# PSU.net
KiCad netlist of a schematic drawn in EAGLE
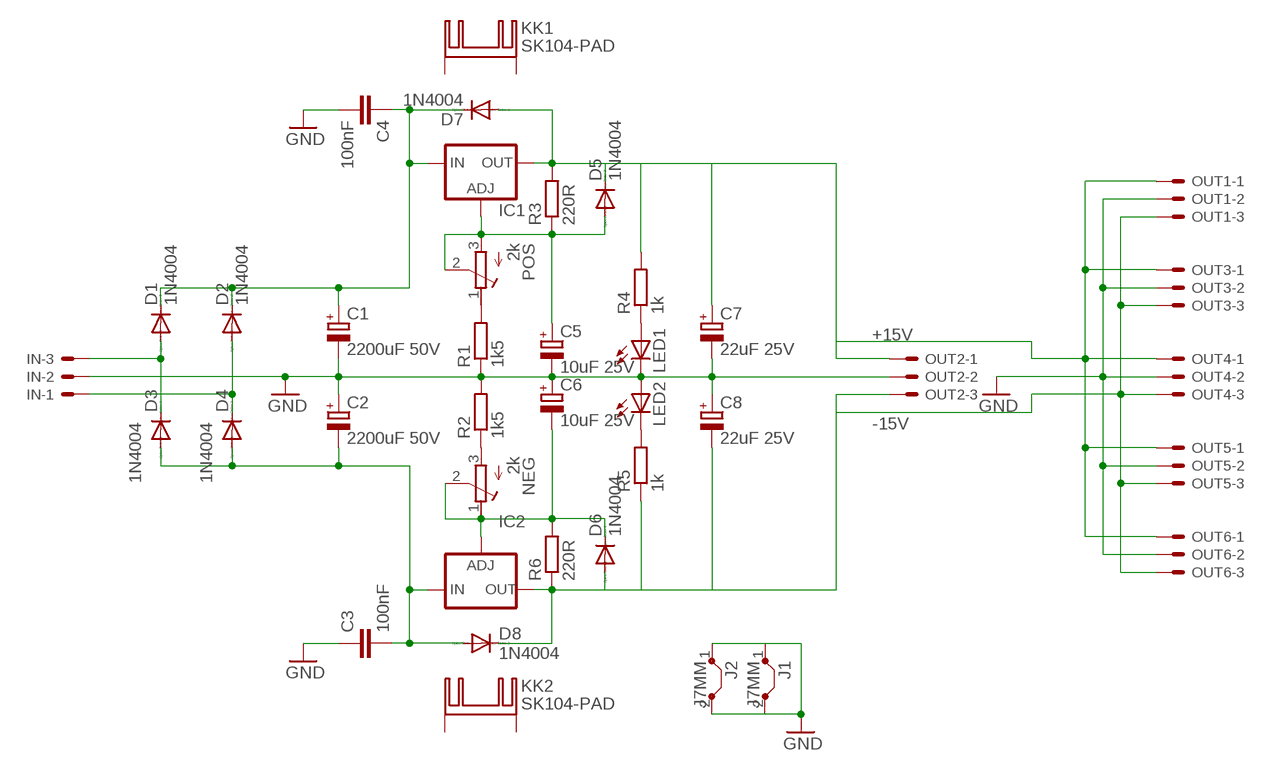
[diagram p0: schematic, sheet 1]

(export (version "E")
  (design (tool "Eeschema 10.0.6"))
  (components
    (comp (ref "C1")
      (value "2200uF 50V")
      (footprint "eagle-import:E7,5-16")
      (libsource (lib "eagle-import") (part "CPOL-EUE7.5-16"))
    )
    (comp (ref "C2")
      (value "2200uF 50V")
      (footprint "eagle-import:E7,5-16")
      (libsource (lib "eagle-import") (part "CPOL-EUE7.5-16"))
    )
    (comp (ref "C3")
      (value "100nF")
      (footprint "eagle-import:C050-025X075")
      (libsource (lib "eagle-import") (part "C-EU050-025X075"))
    )
    (comp (ref "C4")
      (value "100nF")
      (footprint "eagle-import:C050-025X075")
      (libsource (lib "eagle-import") (part "C-EU050-025X075"))
    )
    (comp (ref "C5")
      (value "10uF 25V")
      (footprint "eagle-import:E2,5-5")
      (libsource (lib "eagle-import") (part "CPOL-EUE2.5-5"))
    )
    (comp (ref "C6")
      (value "10uF 25V")
      (footprint "eagle-import:E2,5-5")
      (libsource (lib "eagle-import") (part "CPOL-EUE2.5-5"))
    )
    (comp (ref "C7")
      (value "22uF 25V")
      (footprint "eagle-import:E2,5-5")
      (libsource (lib "eagle-import") (part "CPOL-EUE2.5-5"))
    )
    (comp (ref "C8")
      (value "22uF 25V")
      (footprint "eagle-import:E2,5-5")
      (libsource (lib "eagle-import") (part "CPOL-EUE2.5-5"))
    )
    (comp (ref "D1")
      (value "1N4004")
      (footprint "eagle-import:DO41-10")
      (libsource (lib "eagle-import") (part "1N4004"))
    )
    (comp (ref "D2")
      (value "1N4004")
      (footprint "eagle-import:DO41-10")
      (libsource (lib "eagle-import") (part "1N4004"))
    )
    (comp (ref "D3")
      (value "1N4004")
      (footprint "eagle-import:DO41-10")
      (libsource (lib "eagle-import") (part "1N4004"))
    )
    (comp (ref "D4")
      (value "1N4004")
      (footprint "eagle-import:DO41-10")
      (libsource (lib "eagle-import") (part "1N4004"))
    )
    (comp (ref "D5")
      (value "1N4004")
      (footprint "eagle-import:DO41-10")
      (libsource (lib "eagle-import") (part "1N4004"))
    )
    (comp (ref "D6")
      (value "1N4004")
      (footprint "eagle-import:DO41-10")
      (libsource (lib "eagle-import") (part "1N4004"))
    )
    (comp (ref "D7")
      (value "1N4004")
      (footprint "eagle-import:DO41-10")
      (libsource (lib "eagle-import") (part "1N4004"))
    )
    (comp (ref "D8")
      (value "1N4004")
      (footprint "eagle-import:DO41-10")
      (libsource (lib "eagle-import") (part "1N4004"))
    )
    (comp (ref "IC1")
      (value "LM317TS")
      (footprint "eagle-import:317TS")
      (libsource (lib "eagle-import") (part "LM317TS"))
    )
    (comp (ref "IC2")
      (value "LM337TS")
      (footprint "eagle-import:337TS")
      (libsource (lib "eagle-import") (part "LM337TS"))
    )
    (comp (ref "IN")
      (value "KK-156-3")
      (footprint "eagle-import:KK-156-3")
      (libsource (lib "eagle-import") (part "KK-156-3"))
    )
    (comp (ref "J1")
      (value "J7MM")
      (footprint "eagle-import:07")
      (libsource (lib "eagle-import") (part "J7MM"))
    )
    (comp (ref "J2")
      (value "J7MM")
      (footprint "eagle-import:07")
      (libsource (lib "eagle-import") (part "J7MM"))
    )
    (comp (ref "KK1")
      (value "SK104-PAD")
      (footprint "eagle-import:SK104-PAD")
      (libsource (lib "eagle-import") (part "SK104-PAD"))
    )
    (comp (ref "KK2")
      (value "SK104-PAD")
      (footprint "eagle-import:SK104-PAD")
      (libsource (lib "eagle-import") (part "SK104-PAD"))
    )
    (comp (ref "LED1")
      (value "LED3MM")
      (footprint "eagle-import:LED3MM")
      (libsource (lib "eagle-import") (part "LED3MM"))
    )
    (comp (ref "LED2")
      (value "LED3MM")
      (footprint "eagle-import:LED3MM")
      (libsource (lib "eagle-import") (part "LED3MM"))
    )
    (comp (ref "NEG")
      (value "2k")
      (footprint "eagle-import:RTRIMT93YA")
      (libsource (lib "eagle-import") (part "R-TRIMMT93YA"))
    )
    (comp (ref "OUT1")
      (value "KK-156-3")
      (footprint "eagle-import:KK-156-3")
      (libsource (lib "eagle-import") (part "KK-156-3"))
    )
    (comp (ref "OUT2")
      (value "KK-156-3")
      (footprint "eagle-import:KK-156-3")
      (libsource (lib "eagle-import") (part "KK-156-3"))
    )
    (comp (ref "OUT3")
      (value "KK-156-3")
      (footprint "eagle-import:KK-156-3")
      (libsource (lib "eagle-import") (part "KK-156-3"))
    )
    (comp (ref "OUT4")
      (value "KK-156-3")
      (footprint "eagle-import:KK-156-3")
      (libsource (lib "eagle-import") (part "KK-156-3"))
    )
    (comp (ref "OUT5")
      (value "KK-156-3")
      (footprint "eagle-import:KK-156-3")
      (libsource (lib "eagle-import") (part "KK-156-3"))
    )
    (comp (ref "OUT6")
      (value "KK-156-3")
      (footprint "eagle-import:KK-156-3")
      (libsource (lib "eagle-import") (part "KK-156-3"))
    )
    (comp (ref "POS")
      (value "2k")
      (footprint "eagle-import:RTRIMT93YA")
      (libsource (lib "eagle-import") (part "R-TRIMMT93YA"))
    )
    (comp (ref "R1")
      (value "1k5")
      (footprint "eagle-import:0207_7")
      (libsource (lib "eagle-import") (part "R-EU_0207/7"))
    )
    (comp (ref "R2")
      (value "1k5")
      (footprint "eagle-import:0207_7")
      (libsource (lib "eagle-import") (part "R-EU_0207/7"))
    )
    (comp (ref "R3")
      (value "220R")
      (footprint "eagle-import:0207_7")
      (libsource (lib "eagle-import") (part "R-EU_0207/7"))
    )
    (comp (ref "R4")
      (value "1k")
      (footprint "eagle-import:0207_7")
      (libsource (lib "eagle-import") (part "R-EU_0207/7"))
    )
    (comp (ref "R5")
      (value "1k")
      (footprint "eagle-import:0207_7")
      (libsource (lib "eagle-import") (part "R-EU_0207/7"))
    )
    (comp (ref "R6")
      (value "220R")
      (footprint "eagle-import:0207_7")
      (libsource (lib "eagle-import") (part "R-EU_0207/7"))
    )
  )
  (nets
    (net (code "1") (name "/+15V") (class "Default")
      (node (ref "C7") (pin "+") (pinfunction "+_+") (pintype "passive"))
      (node (ref "D5") (pin "C") (pinfunction "C_C") (pintype "passive"))
      (node (ref "D7") (pin "A") (pinfunction "A_A") (pintype "passive"))
      (node (ref "IC1") (pin "2") (pinfunction "OUT_2") (pintype "passive"))
      (node (ref "OUT1") (pin "1") (pinfunction "S_1") (pintype "passive"))
      (node (ref "OUT2") (pin "1") (pinfunction "S_1") (pintype "passive"))
      (node (ref "OUT3") (pin "1") (pinfunction "S_1") (pintype "passive"))
      (node (ref "OUT4") (pin "1") (pinfunction "S_1") (pintype "passive"))
      (node (ref "OUT5") (pin "1") (pinfunction "S_1") (pintype "passive"))
      (node (ref "OUT6") (pin "1") (pinfunction "S_1") (pintype "passive"))
      (node (ref "R3") (pin "2") (pinfunction "2_2") (pintype "passive"))
      (node (ref "R4") (pin "2") (pinfunction "2_2") (pintype "passive"))
    )
    (net (code "2") (name "/-15V") (class "Default")
      (node (ref "C8") (pin "-") (pinfunction "-_-") (pintype "passive"))
      (node (ref "D6") (pin "A") (pinfunction "A_A") (pintype "passive"))
      (node (ref "D8") (pin "C") (pinfunction "C_C") (pintype "passive"))
      (node (ref "IC2") (pin "3") (pinfunction "OUT_3") (pintype "passive"))
      (node (ref "OUT1") (pin "3") (pinfunction "S_3") (pintype "passive"))
      (node (ref "OUT2") (pin "3") (pinfunction "S_3") (pintype "passive"))
      (node (ref "OUT3") (pin "3") (pinfunction "S_3") (pintype "passive"))
      (node (ref "OUT4") (pin "3") (pinfunction "S_3") (pintype "passive"))
      (node (ref "OUT5") (pin "3") (pinfunction "S_3") (pintype "passive"))
      (node (ref "OUT6") (pin "3") (pinfunction "S_3") (pintype "passive"))
      (node (ref "R5") (pin "1") (pinfunction "1_1") (pintype "passive"))
      (node (ref "R6") (pin "1") (pinfunction "1_1") (pintype "passive"))
    )
    (net (code "3") (name "GND") (class "Default")
      (node (ref "C1") (pin "-") (pinfunction "-_-") (pintype "passive"))
      (node (ref "C2") (pin "+") (pinfunction "+_+") (pintype "passive"))
      (node (ref "C3") (pin "1") (pinfunction "1_1") (pintype "passive"))
      (node (ref "C4") (pin "2") (pinfunction "2_2") (pintype "passive"))
      (node (ref "C5") (pin "-") (pinfunction "-_-") (pintype "passive"))
      (node (ref "C6") (pin "+") (pinfunction "+_+") (pintype "passive"))
      (node (ref "C7") (pin "-") (pinfunction "-_-") (pintype "passive"))
      (node (ref "C8") (pin "+") (pinfunction "+_+") (pintype "passive"))
      (node (ref "IN") (pin "2") (pinfunction "S_2") (pintype "passive"))
      (node (ref "J1") (pin "1") (pinfunction "1_1") (pintype "passive"))
      (node (ref "J1") (pin "2") (pinfunction "2_2") (pintype "passive"))
      (node (ref "J2") (pin "1") (pinfunction "1_1") (pintype "passive"))
      (node (ref "J2") (pin "2") (pinfunction "2_2") (pintype "passive"))
      (node (ref "LED1") (pin "K") (pinfunction "C_K") (pintype "passive"))
      (node (ref "LED2") (pin "A") (pinfunction "A_A") (pintype "passive"))
      (node (ref "OUT1") (pin "2") (pinfunction "S_2") (pintype "passive"))
      (node (ref "OUT2") (pin "2") (pinfunction "S_2") (pintype "passive"))
      (node (ref "OUT3") (pin "2") (pinfunction "S_2") (pintype "passive"))
      (node (ref "OUT4") (pin "2") (pinfunction "S_2") (pintype "passive"))
      (node (ref "OUT5") (pin "2") (pinfunction "S_2") (pintype "passive"))
      (node (ref "OUT6") (pin "2") (pinfunction "S_2") (pintype "passive"))
      (node (ref "R1") (pin "1") (pinfunction "1_1") (pintype "passive"))
      (node (ref "R2") (pin "2") (pinfunction "2_2") (pintype "passive"))
    )
    (net (code "4") (name "Net-(IC1-ADJ)") (class "Default")
      (node (ref "C5") (pin "+") (pinfunction "+_+") (pintype "passive"))
      (node (ref "D5") (pin "A") (pinfunction "A_A") (pintype "passive"))
      (node (ref "IC1") (pin "1") (pinfunction "ADJ_1") (pintype "input"))
      (node (ref "POS") (pin "2") (pinfunction "S_2") (pintype "passive"))
      (node (ref "POS") (pin "3") (pinfunction "A_3") (pintype "passive"))
      (node (ref "R3") (pin "1") (pinfunction "1_1") (pintype "passive"))
    )
    (net (code "5") (name "Net-(IC1-IN)") (class "Default")
      (node (ref "C1") (pin "+") (pinfunction "+_+") (pintype "passive"))
      (node (ref "C4") (pin "1") (pinfunction "1_1") (pintype "passive"))
      (node (ref "D1") (pin "C") (pinfunction "C_C") (pintype "passive"))
      (node (ref "D2") (pin "C") (pinfunction "C_C") (pintype "passive"))
      (node (ref "D7") (pin "C") (pinfunction "C_C") (pintype "passive"))
      (node (ref "IC1") (pin "3") (pinfunction "IN_3") (pintype "input"))
    )
    (net (code "6") (name "Net-(IC2-ADJ)") (class "Default")
      (node (ref "C6") (pin "-") (pinfunction "-_-") (pintype "passive"))
      (node (ref "D6") (pin "C") (pinfunction "C_C") (pintype "passive"))
      (node (ref "IC2") (pin "1") (pinfunction "ADJ_1") (pintype "input"))
      (node (ref "NEG") (pin "1") (pinfunction "E_1") (pintype "passive"))
      (node (ref "NEG") (pin "2") (pinfunction "S_2") (pintype "passive"))
      (node (ref "R6") (pin "2") (pinfunction "2_2") (pintype "passive"))
    )
    (net (code "7") (name "Net-(IC2-IN)") (class "Default")
      (node (ref "C2") (pin "-") (pinfunction "-_-") (pintype "passive"))
      (node (ref "C3") (pin "2") (pinfunction "2_2") (pintype "passive"))
      (node (ref "D3") (pin "A") (pinfunction "A_A") (pintype "passive"))
      (node (ref "D4") (pin "A") (pinfunction "A_A") (pintype "passive"))
      (node (ref "D8") (pin "A") (pinfunction "A_A") (pintype "passive"))
      (node (ref "IC2") (pin "2") (pinfunction "IN_2") (pintype "input"))
    )
    (net (code "8") (name "Net-(INA-S)") (class "Default")
      (node (ref "D2") (pin "A") (pinfunction "A_A") (pintype "passive"))
      (node (ref "D4") (pin "C") (pinfunction "C_C") (pintype "passive"))
      (node (ref "IN") (pin "1") (pinfunction "S_1") (pintype "passive"))
    )
    (net (code "9") (name "Net-(INC-S)") (class "Default")
      (node (ref "D1") (pin "A") (pinfunction "A_A") (pintype "passive"))
      (node (ref "D3") (pin "C") (pinfunction "C_C") (pintype "passive"))
      (node (ref "IN") (pin "3") (pinfunction "S_3") (pintype "passive"))
    )
    (net (code "10") (name "Net-(LED1-PadA)") (class "Default")
      (node (ref "LED1") (pin "A") (pinfunction "A_A") (pintype "passive"))
      (node (ref "R4") (pin "1") (pinfunction "1_1") (pintype "passive"))
    )
    (net (code "11") (name "Net-(LED2-C)") (class "Default")
      (node (ref "LED2") (pin "K") (pinfunction "C_K") (pintype "passive"))
      (node (ref "R5") (pin "2") (pinfunction "2_2") (pintype "passive"))
    )
    (net (code "12") (name "Net-(NEG-A)") (class "Default")
      (node (ref "NEG") (pin "3") (pinfunction "A_3") (pintype "passive"))
      (node (ref "R2") (pin "1") (pinfunction "1_1") (pintype "passive"))
    )
    (net (code "13") (name "Net-(POS-E)") (class "Default")
      (node (ref "POS") (pin "1") (pinfunction "E_1") (pintype "passive"))
      (node (ref "R1") (pin "2") (pinfunction "2_2") (pintype "passive"))
    )
    (net (code "14") (name "unconnected-(KK1-K-PadK1)") (class "Default")
      (node (ref "KK1") (pin "K1") (pinfunction "K_K1") (pintype "passive"))
    )
    (net (code "15") (name "unconnected-(KK1-K-PadK2)") (class "Default")
      (node (ref "KK1") (pin "K2") (pinfunction "K_K2") (pintype "passive"))
    )
    (net (code "16") (name "unconnected-(KK2-K-PadK1)") (class "Default")
      (node (ref "KK2") (pin "K1") (pinfunction "K_K1") (pintype "passive"))
    )
    (net (code "17") (name "unconnected-(KK2-K-PadK2)") (class "Default")
      (node (ref "KK2") (pin "K2") (pinfunction "K_K2") (pintype "passive"))
    )
  )
)
